# Power_Supply.net
KiCad netlist of a schematic drawn in Altium Designer
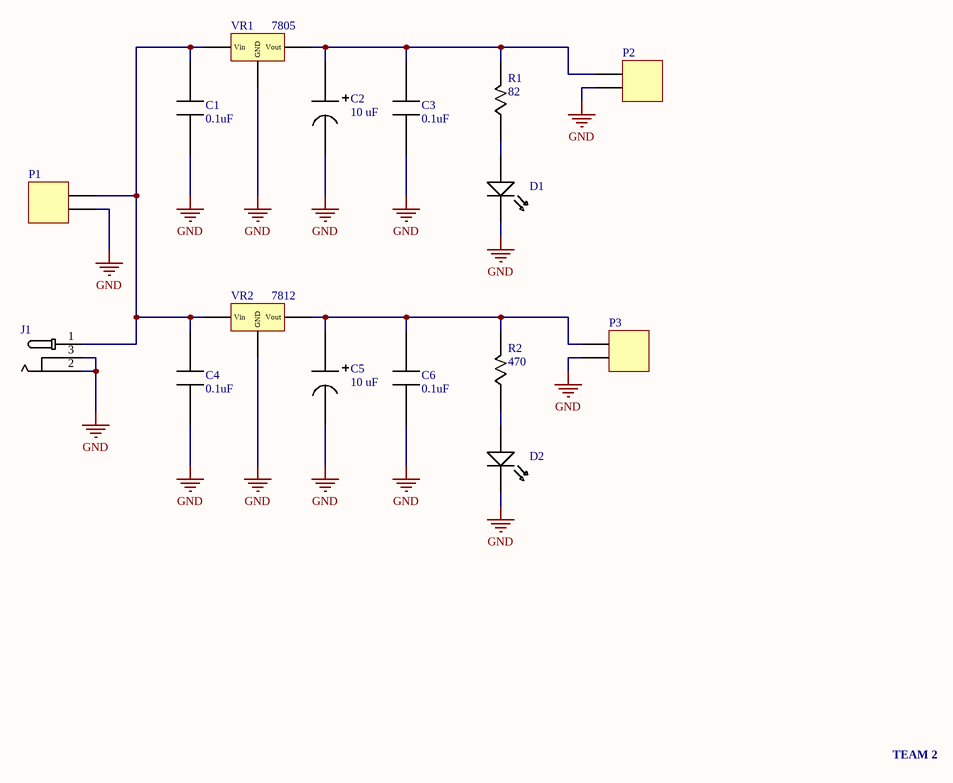
[diagram p0: Power Supply.SchDoc]

(export (version "E")
  (design (tool "Eeschema 10.0.6"))
  (components
    (comp (ref "C1")
      (value "0.1uF")
      (footprint "CAPACITOR")
      (fields (field (name "MANUFACTURE PART NUMBER") "AR205F104K4R"))
      (libsource (lib "Power Supply") (part "CAPACITOR"))
    )
    (comp (ref "C2")
      (value "10 uF")
      (footprint "POL CAP")
      (fields (field (name "MANUFACTURE PART NUMBER") "EEUEB1J100SB"))
      (libsource (lib "Power Supply") (part "POL CAP"))
    )
    (comp (ref "C3")
      (value "0.1uF")
      (footprint "CAPACITOR")
      (fields (field (name "MANUFACTURE PART NUMBER") "AR205F104K4R"))
      (libsource (lib "Power Supply") (part "CAPACITOR"))
    )
    (comp (ref "C4")
      (value "0.1uF")
      (footprint "CAPACITOR")
      (fields (field (name "MANUFACTURE PART NUMBER") "AR205F104K4R"))
      (libsource (lib "Power Supply") (part "CAPACITOR"))
    )
    (comp (ref "C5")
      (value "10 uF")
      (footprint "POL CAP")
      (fields (field (name "MANUFACTURE PART NUMBER") "EEUEB1J100SB"))
      (libsource (lib "Power Supply") (part "POL CAP"))
    )
    (comp (ref "C6")
      (value "0.1uF")
      (footprint "CAPACITOR")
      (fields (field (name "MANUFACTURE PART NUMBER") "AR205F104K4R"))
      (libsource (lib "Power Supply") (part "CAPACITOR"))
    )
    (comp (ref "D1")
      (value "LED")
      (footprint "LED")
      (fields (field (name "MANUFACTURE PART NUMBER") "151033GS03000"))
      (libsource (lib "Power Supply") (part "LED"))
    )
    (comp (ref "D2")
      (value "LED")
      (footprint "LED")
      (fields (field (name "MANUFACTURE PART NUMBER") "151033GS03000"))
      (libsource (lib "Power Supply") (part "LED"))
    )
    (comp (ref "J1")
      (value "POWER JACK SOCKET")
      (footprint "POWER JACK SOCKET")
      (fields (field (name "MANUFACTURE PART NUMBER") "EJ508A"))
      (libsource (lib "Power Supply") (part "POWER JACK SOCKET"))
    )
    (comp (ref "P1")
      (value "TERMINAL BLOCK")
      (footprint "TERMINAL BLOCK")
      (libsource (lib "") (part "TERMINAL BLOCK_1"))
    )
    (comp (ref "P2")
      (value "TERMINAL BLOCK")
      (footprint "TERMINAL BLOCK")
      (libsource (lib "Power Supply") (part "TERMINAL BLOCK"))
    )
    (comp (ref "P3")
      (value "TERMINAL BLOCK")
      (footprint "TERMINAL BLOCK")
      (libsource (lib "Power Supply") (part "TERMINAL BLOCK"))
    )
    (comp (ref "R1") (value "82") (footprint "RESISTOR") (libsource (lib "Power Supply") (part "RESISTOR")))
    (comp (ref "R2") (value "470") (footprint "RESISTOR") (libsource (lib "Power Supply") (part "RESISTOR")))
    (comp (ref "VR1")
      (value "7805")
      (footprint "REGULATOR7805")
      (fields (field (name "MANUFACTURE PART NUMBER") "7805CV"))
      (libsource (lib "Power Supply") (part "7805"))
    )
    (comp (ref "VR2")
      (value "7812")
      (footprint "REGULATOR7812")
      (fields (field (name "MANUFACTURE PART NUMBER") "L7812CV"))
      (libsource (lib "Power Supply") (part "7812"))
    )
  )
  (nets
    (net (code "1") (name "GND") (class "Default")
      (node (ref "C1") (pin "2") (pinfunction "2_2") (pintype "passive"))
      (node (ref "C2") (pin "2") (pinfunction "2_2") (pintype "passive"))
      (node (ref "C3") (pin "2") (pinfunction "2_2") (pintype "passive"))
      (node (ref "C4") (pin "2") (pinfunction "2_2") (pintype "passive"))
      (node (ref "C5") (pin "2") (pinfunction "2_2") (pintype "passive"))
      (node (ref "C6") (pin "2") (pinfunction "2_2") (pintype "passive"))
      (node (ref "D1") (pin "2") (pinfunction "2_2") (pintype "passive"))
      (node (ref "D2") (pin "2") (pinfunction "2_2") (pintype "passive"))
      (node (ref "J1") (pin "2") (pinfunction "2_2") (pintype "passive"))
      (node (ref "J1") (pin "3") (pinfunction "3_3") (pintype "passive"))
      (node (ref "P1") (pin "2") (pinfunction "2_2") (pintype "passive"))
      (node (ref "P2") (pin "1") (pinfunction "1_1") (pintype "passive"))
      (node (ref "P3") (pin "1") (pinfunction "1_1") (pintype "passive"))
      (node (ref "VR1") (pin "3") (pinfunction "GND_3") (pintype "passive"))
      (node (ref "VR2") (pin "3") (pinfunction "GND_3") (pintype "passive"))
    )
    (net (code "2") (name "Net-(D1-Pad1)") (class "Default")
      (node (ref "D1") (pin "1") (pinfunction "1_1") (pintype "passive"))
      (node (ref "R1") (pin "1") (pinfunction "1_1") (pintype "passive"))
    )
    (net (code "3") (name "Net-(D2-Pad1)") (class "Default")
      (node (ref "D2") (pin "1") (pinfunction "1_1") (pintype "passive"))
      (node (ref "R2") (pin "1") (pinfunction "1_1") (pintype "passive"))
    )
    (net (code "4") (name "Net-(VR1-Vin)") (class "Default")
      (node (ref "C1") (pin "1") (pinfunction "1_1") (pintype "passive"))
      (node (ref "C4") (pin "1") (pinfunction "1_1") (pintype "passive"))
      (node (ref "J1") (pin "1") (pinfunction "1_1") (pintype "passive"))
      (node (ref "P1") (pin "1") (pinfunction "1_1") (pintype "passive"))
      (node (ref "VR1") (pin "1") (pinfunction "Vin_1") (pintype "passive"))
      (node (ref "VR2") (pin "1") (pinfunction "Vin_1") (pintype "passive"))
    )
    (net (code "5") (name "Net-(VR1-Vout)") (class "Default")
      (node (ref "C2") (pin "1") (pinfunction "1_1") (pintype "passive"))
      (node (ref "C3") (pin "1") (pinfunction "1_1") (pintype "passive"))
      (node (ref "P2") (pin "2") (pinfunction "2_2") (pintype "passive"))
      (node (ref "R1") (pin "2") (pinfunction "2_2") (pintype "passive"))
      (node (ref "VR1") (pin "2") (pinfunction "Vout_2") (pintype "passive"))
    )
    (net (code "6") (name "Net-(VR2-Vout)") (class "Default")
      (node (ref "C5") (pin "1") (pinfunction "1_1") (pintype "passive"))
      (node (ref "C6") (pin "1") (pinfunction "1_1") (pintype "passive"))
      (node (ref "P3") (pin "2") (pinfunction "2_2") (pintype "passive"))
      (node (ref "R2") (pin "2") (pinfunction "2_2") (pintype "passive"))
      (node (ref "VR2") (pin "2") (pinfunction "Vout_2") (pintype "passive"))
    )
  )
)
